# ledstick.net
KiCad netlist of a schematic drawn in EAGLE
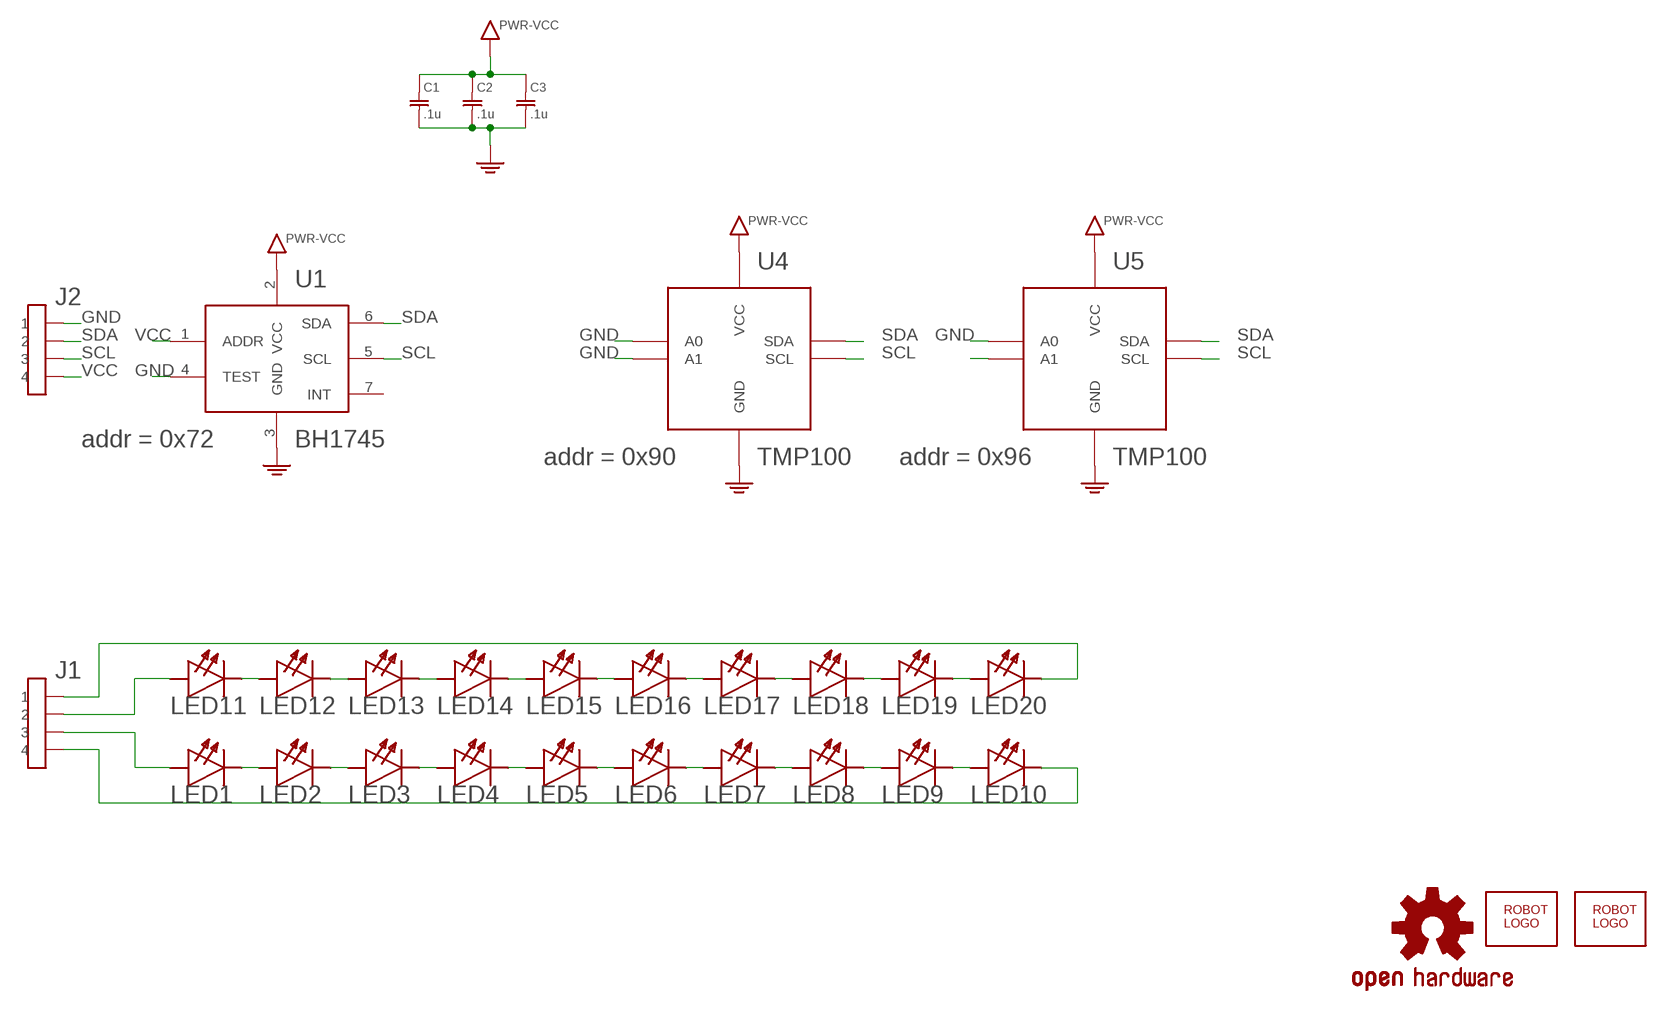
[diagram p0: schematic, sheet 1]

(export (version "E")
  (design (tool "Eeschema 10.0.6"))
  (components
    (comp (ref "C1")
      (value ".1u")
      (footprint "eagle-import:SMD0603")
      (libsource (lib "eagle-import") (part "C0603"))
    )
    (comp (ref "C2")
      (value ".1u")
      (footprint "eagle-import:SMD0603")
      (libsource (lib "eagle-import") (part "C0603"))
    )
    (comp (ref "C3")
      (value ".1u")
      (footprint "eagle-import:SMD0603")
      (libsource (lib "eagle-import") (part "C0603"))
    )
    (comp (ref "J1")
      (value "HEADER-4X1-PTH")
      (footprint "eagle-import:HEADER-4X1-PTH")
      (libsource (lib "eagle-import") (part "HEADER-4X1-PTH"))
    )
    (comp (ref "J2")
      (value "HEADER-4X1-PTH")
      (footprint "eagle-import:HEADER-4X1-PTH")
      (libsource (lib "eagle-import") (part "HEADER-4X1-PTH"))
    )
    (comp (ref "LED1")
      (value "W")
      (footprint "eagle-import:LED4-4P1A")
      (libsource (lib "eagle-import") (part "LED-L4-P1A"))
    )
    (comp (ref "LED2")
      (value "W")
      (footprint "eagle-import:LED4-4P1A")
      (libsource (lib "eagle-import") (part "LED-L4-P1A"))
    )
    (comp (ref "LED3")
      (value "W")
      (footprint "eagle-import:LED4-4P1A")
      (libsource (lib "eagle-import") (part "LED-L4-P1A"))
    )
    (comp (ref "LED4")
      (value "W")
      (footprint "eagle-import:LED4-4P1A")
      (libsource (lib "eagle-import") (part "LED-L4-P1A"))
    )
    (comp (ref "LED5")
      (value "W")
      (footprint "eagle-import:LED4-4P1A")
      (libsource (lib "eagle-import") (part "LED-L4-P1A"))
    )
    (comp (ref "LED6")
      (value "W")
      (footprint "eagle-import:LED4-4P1A")
      (libsource (lib "eagle-import") (part "LED-L4-P1A"))
    )
    (comp (ref "LED7")
      (value "W")
      (footprint "eagle-import:LED4-4P1A")
      (libsource (lib "eagle-import") (part "LED-L4-P1A"))
    )
    (comp (ref "LED8")
      (value "W")
      (footprint "eagle-import:LED4-4P1A")
      (libsource (lib "eagle-import") (part "LED-L4-P1A"))
    )
    (comp (ref "LED9")
      (value "W")
      (footprint "eagle-import:LED4-4P1A")
      (libsource (lib "eagle-import") (part "LED-L4-P1A"))
    )
    (comp (ref "LED10")
      (value "W")
      (footprint "eagle-import:LED4-4P1A")
      (libsource (lib "eagle-import") (part "LED-L4-P1A"))
    )
    (comp (ref "LED11")
      (value "C")
      (footprint "eagle-import:LED4-4P1A")
      (libsource (lib "eagle-import") (part "LED-L4-P1A"))
    )
    (comp (ref "LED12")
      (value "C")
      (footprint "eagle-import:LED4-4P1A")
      (libsource (lib "eagle-import") (part "LED-L4-P1A"))
    )
    (comp (ref "LED13")
      (value "C")
      (footprint "eagle-import:LED4-4P1A")
      (libsource (lib "eagle-import") (part "LED-L4-P1A"))
    )
    (comp (ref "LED14")
      (value "C")
      (footprint "eagle-import:LED4-4P1A")
      (libsource (lib "eagle-import") (part "LED-L4-P1A"))
    )
    (comp (ref "LED15")
      (value "C")
      (footprint "eagle-import:LED4-4P1A")
      (libsource (lib "eagle-import") (part "LED-L4-P1A"))
    )
    (comp (ref "LED16")
      (value "C")
      (footprint "eagle-import:LED4-4P1A")
      (libsource (lib "eagle-import") (part "LED-L4-P1A"))
    )
    (comp (ref "LED17")
      (value "C")
      (footprint "eagle-import:LED4-4P1A")
      (libsource (lib "eagle-import") (part "LED-L4-P1A"))
    )
    (comp (ref "LED18")
      (value "C")
      (footprint "eagle-import:LED4-4P1A")
      (libsource (lib "eagle-import") (part "LED-L4-P1A"))
    )
    (comp (ref "LED19")
      (value "C")
      (footprint "eagle-import:LED4-4P1A")
      (libsource (lib "eagle-import") (part "LED-L4-P1A"))
    )
    (comp (ref "LED20")
      (value "C")
      (footprint "eagle-import:LED4-4P1A")
      (libsource (lib "eagle-import") (part "LED-L4-P1A"))
    )
    (comp (ref "LOGO1")
      (value "OSHW-LOGOM")
      (footprint "eagle-import:OSHW-LOGO-M")
      (libsource (lib "eagle-import") (part "OSHW-LOGOM"))
    )
    (comp (ref "U$1")
      (value "ROBOTMAN-LOGO")
      (footprint "eagle-import:ROBOTMAN-LOGO")
      (libsource (lib "eagle-import") (part "ROBOTMAN-LOGO"))
    )
    (comp (ref "U$2")
      (value "ROBOTMAN-LOGO")
      (footprint "eagle-import:ROBOTMAN-LOGO")
      (libsource (lib "eagle-import") (part "ROBOTMAN-LOGO"))
    )
    (comp (ref "U1")
      (value "BH1745")
      (footprint "eagle-import:WSON8")
      (libsource (lib "eagle-import") (part "BH1745"))
    )
    (comp (ref "U4")
      (value "TMP100")
      (footprint "eagle-import:SOT-23-6")
      (libsource (lib "eagle-import") (part "TMP100"))
    )
    (comp (ref "U5")
      (value "TMP100")
      (footprint "eagle-import:SOT-23-6")
      (libsource (lib "eagle-import") (part "TMP100"))
    )
  )
  (nets
    (net (code "1") (name "/SCL") (class "Default")
      (node (ref "J2") (pin "P$3") (pinfunction "3_P$3") (pintype "bidirectional"))
      (node (ref "U1") (pin "5") (pinfunction "SCL_5") (pintype "bidirectional"))
      (node (ref "U4") (pin "1") (pinfunction "SCL_1") (pintype "bidirectional"))
      (node (ref "U5") (pin "1") (pinfunction "SCL_1") (pintype "bidirectional"))
    )
    (net (code "2") (name "/SDA") (class "Default")
      (node (ref "J2") (pin "P$2") (pinfunction "2_P$2") (pintype "bidirectional"))
      (node (ref "U1") (pin "6") (pinfunction "SDA_6") (pintype "bidirectional"))
      (node (ref "U4") (pin "6") (pinfunction "SDA_6") (pintype "bidirectional"))
      (node (ref "U5") (pin "6") (pinfunction "SDA_6") (pintype "bidirectional"))
    )
    (net (code "3") (name "Net-(J1-1)") (class "Default")
      (node (ref "J1") (pin "P$1") (pinfunction "1_P$1") (pintype "bidirectional"))
      (node (ref "LED20") (pin "C") (pinfunction "C_C") (pintype "passive"))
    )
    (net (code "4") (name "Net-(J1-2)") (class "Default")
      (node (ref "J1") (pin "P$2") (pinfunction "2_P$2") (pintype "bidirectional"))
      (node (ref "LED11") (pin "A") (pinfunction "A_A") (pintype "passive"))
      (node (ref "LED11") (pin "AP") (pinfunction "A_AP") (pintype "passive"))
    )
    (net (code "5") (name "Net-(J1-3)") (class "Default")
      (node (ref "J1") (pin "P$3") (pinfunction "3_P$3") (pintype "bidirectional"))
      (node (ref "LED1") (pin "A") (pinfunction "A_A") (pintype "passive"))
      (node (ref "LED1") (pin "AP") (pinfunction "A_AP") (pintype "passive"))
    )
    (net (code "6") (name "Net-(J1-4)") (class "Default")
      (node (ref "J1") (pin "P$4") (pinfunction "4_P$4") (pintype "bidirectional"))
      (node (ref "LED10") (pin "C") (pinfunction "C_C") (pintype "passive"))
    )
    (net (code "7") (name "Net-(LED1-PadC)") (class "Default")
      (node (ref "LED1") (pin "C") (pinfunction "C_C") (pintype "passive"))
      (node (ref "LED2") (pin "A") (pinfunction "A_A") (pintype "passive"))
      (node (ref "LED2") (pin "AP") (pinfunction "A_AP") (pintype "passive"))
    )
    (net (code "8") (name "Net-(LED2-PadC)") (class "Default")
      (node (ref "LED2") (pin "C") (pinfunction "C_C") (pintype "passive"))
      (node (ref "LED3") (pin "A") (pinfunction "A_A") (pintype "passive"))
      (node (ref "LED3") (pin "AP") (pinfunction "A_AP") (pintype "passive"))
    )
    (net (code "9") (name "Net-(LED3-PadC)") (class "Default")
      (node (ref "LED3") (pin "C") (pinfunction "C_C") (pintype "passive"))
      (node (ref "LED4") (pin "A") (pinfunction "A_A") (pintype "passive"))
      (node (ref "LED4") (pin "AP") (pinfunction "A_AP") (pintype "passive"))
    )
    (net (code "10") (name "Net-(LED4-PadC)") (class "Default")
      (node (ref "LED4") (pin "C") (pinfunction "C_C") (pintype "passive"))
      (node (ref "LED5") (pin "A") (pinfunction "A_A") (pintype "passive"))
      (node (ref "LED5") (pin "AP") (pinfunction "A_AP") (pintype "passive"))
    )
    (net (code "11") (name "Net-(LED5-PadC)") (class "Default")
      (node (ref "LED5") (pin "C") (pinfunction "C_C") (pintype "passive"))
      (node (ref "LED6") (pin "A") (pinfunction "A_A") (pintype "passive"))
      (node (ref "LED6") (pin "AP") (pinfunction "A_AP") (pintype "passive"))
    )
    (net (code "12") (name "Net-(LED6-PadC)") (class "Default")
      (node (ref "LED6") (pin "C") (pinfunction "C_C") (pintype "passive"))
      (node (ref "LED7") (pin "A") (pinfunction "A_A") (pintype "passive"))
      (node (ref "LED7") (pin "AP") (pinfunction "A_AP") (pintype "passive"))
    )
    (net (code "13") (name "Net-(LED7-PadC)") (class "Default")
      (node (ref "LED7") (pin "C") (pinfunction "C_C") (pintype "passive"))
      (node (ref "LED8") (pin "A") (pinfunction "A_A") (pintype "passive"))
      (node (ref "LED8") (pin "AP") (pinfunction "A_AP") (pintype "passive"))
    )
    (net (code "14") (name "Net-(LED8-PadC)") (class "Default")
      (node (ref "LED8") (pin "C") (pinfunction "C_C") (pintype "passive"))
      (node (ref "LED9") (pin "A") (pinfunction "A_A") (pintype "passive"))
      (node (ref "LED9") (pin "AP") (pinfunction "A_AP") (pintype "passive"))
    )
    (net (code "15") (name "Net-(LED10-A-PadAP)") (class "Default")
      (node (ref "LED10") (pin "A") (pinfunction "A_A") (pintype "passive"))
      (node (ref "LED10") (pin "AP") (pinfunction "A_AP") (pintype "passive"))
      (node (ref "LED9") (pin "C") (pinfunction "C_C") (pintype "passive"))
    )
    (net (code "16") (name "Net-(LED11-PadC)") (class "Default")
      (node (ref "LED11") (pin "C") (pinfunction "C_C") (pintype "passive"))
      (node (ref "LED12") (pin "A") (pinfunction "A_A") (pintype "passive"))
      (node (ref "LED12") (pin "AP") (pinfunction "A_AP") (pintype "passive"))
    )
    (net (code "17") (name "Net-(LED12-PadC)") (class "Default")
      (node (ref "LED12") (pin "C") (pinfunction "C_C") (pintype "passive"))
      (node (ref "LED13") (pin "A") (pinfunction "A_A") (pintype "passive"))
      (node (ref "LED13") (pin "AP") (pinfunction "A_AP") (pintype "passive"))
    )
    (net (code "18") (name "Net-(LED13-PadC)") (class "Default")
      (node (ref "LED13") (pin "C") (pinfunction "C_C") (pintype "passive"))
      (node (ref "LED14") (pin "A") (pinfunction "A_A") (pintype "passive"))
      (node (ref "LED14") (pin "AP") (pinfunction "A_AP") (pintype "passive"))
    )
    (net (code "19") (name "Net-(LED14-PadC)") (class "Default")
      (node (ref "LED14") (pin "C") (pinfunction "C_C") (pintype "passive"))
      (node (ref "LED15") (pin "A") (pinfunction "A_A") (pintype "passive"))
      (node (ref "LED15") (pin "AP") (pinfunction "A_AP") (pintype "passive"))
    )
    (net (code "20") (name "Net-(LED15-PadC)") (class "Default")
      (node (ref "LED15") (pin "C") (pinfunction "C_C") (pintype "passive"))
      (node (ref "LED16") (pin "A") (pinfunction "A_A") (pintype "passive"))
      (node (ref "LED16") (pin "AP") (pinfunction "A_AP") (pintype "passive"))
    )
    (net (code "21") (name "Net-(LED16-PadC)") (class "Default")
      (node (ref "LED16") (pin "C") (pinfunction "C_C") (pintype "passive"))
      (node (ref "LED17") (pin "A") (pinfunction "A_A") (pintype "passive"))
      (node (ref "LED17") (pin "AP") (pinfunction "A_AP") (pintype "passive"))
    )
    (net (code "22") (name "Net-(LED17-PadC)") (class "Default")
      (node (ref "LED17") (pin "C") (pinfunction "C_C") (pintype "passive"))
      (node (ref "LED18") (pin "A") (pinfunction "A_A") (pintype "passive"))
      (node (ref "LED18") (pin "AP") (pinfunction "A_AP") (pintype "passive"))
    )
    (net (code "23") (name "Net-(LED18-PadC)") (class "Default")
      (node (ref "LED18") (pin "C") (pinfunction "C_C") (pintype "passive"))
      (node (ref "LED19") (pin "A") (pinfunction "A_A") (pintype "passive"))
      (node (ref "LED19") (pin "AP") (pinfunction "A_AP") (pintype "passive"))
    )
    (net (code "24") (name "Net-(LED19-PadC)") (class "Default")
      (node (ref "LED19") (pin "C") (pinfunction "C_C") (pintype "passive"))
      (node (ref "LED20") (pin "A") (pinfunction "A_A") (pintype "passive"))
      (node (ref "LED20") (pin "AP") (pinfunction "A_AP") (pintype "passive"))
    )
    (net (code "25") (name "PWR-GND") (class "Default")
      (node (ref "C1") (pin "2") (pinfunction "P$2_2") (pintype "passive"))
      (node (ref "C2") (pin "2") (pinfunction "P$2_2") (pintype "passive"))
      (node (ref "C3") (pin "2") (pinfunction "P$2_2") (pintype "passive"))
      (node (ref "J2") (pin "P$1") (pinfunction "1_P$1") (pintype "bidirectional"))
      (node (ref "U1") (pin "3") (pinfunction "GND_3") (pintype "bidirectional"))
      (node (ref "U1") (pin "4") (pinfunction "TEST_4") (pintype "bidirectional"))
      (node (ref "U4") (pin "2") (pinfunction "GND_2") (pintype "bidirectional"))
      (node (ref "U4") (pin "3") (pinfunction "A1_3") (pintype "bidirectional"))
      (node (ref "U4") (pin "5") (pinfunction "A0_5") (pintype "bidirectional"))
      (node (ref "U5") (pin "2") (pinfunction "GND_2") (pintype "bidirectional"))
      (node (ref "U5") (pin "5") (pinfunction "A0_5") (pintype "bidirectional"))
    )
    (net (code "26") (name "PWR-VCC") (class "Default")
      (node (ref "C1") (pin "1") (pinfunction "P$1_1") (pintype "passive"))
      (node (ref "C2") (pin "1") (pinfunction "P$1_1") (pintype "passive"))
      (node (ref "C3") (pin "1") (pinfunction "P$1_1") (pintype "passive"))
      (node (ref "J2") (pin "P$4") (pinfunction "4_P$4") (pintype "bidirectional"))
      (node (ref "U1") (pin "1") (pinfunction "ADDR_1") (pintype "bidirectional"))
      (node (ref "U1") (pin "2") (pinfunction "VCC_2") (pintype "bidirectional"))
      (node (ref "U4") (pin "4") (pinfunction "VCC_4") (pintype "bidirectional"))
      (node (ref "U5") (pin "4") (pinfunction "VCC_4") (pintype "bidirectional"))
    )
    (net (code "27") (name "unconnected-(U1-INT-Pad7)") (class "Default")
      (node (ref "U1") (pin "7") (pinfunction "INT_7") (pintype "bidirectional"))
    )
    (net (code "28") (name "unconnected-(U5-A1-Pad3)") (class "Default")
      (node (ref "U5") (pin "3") (pinfunction "A1_3") (pintype "bidirectional"))
    )
  )
)
